# Serial_Hub.net
KiCad netlist of a schematic drawn in Altium Designer
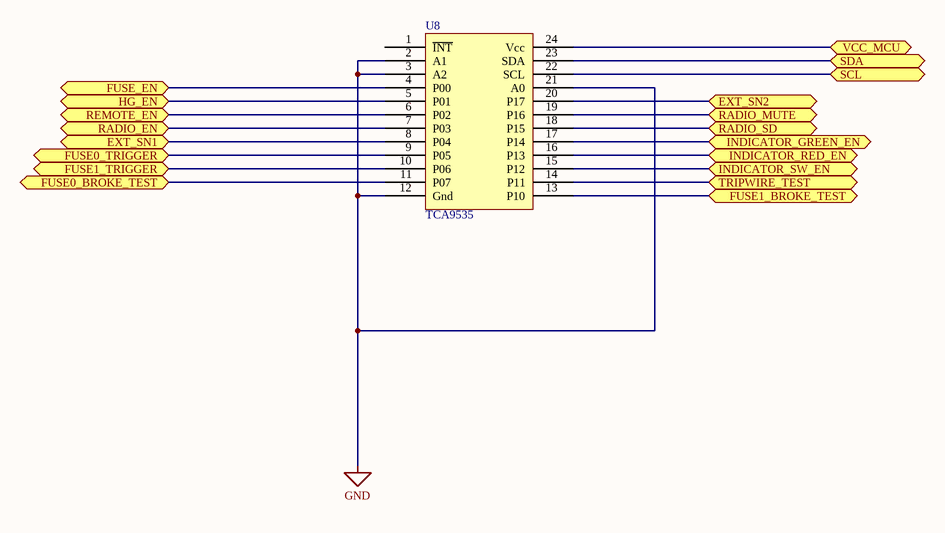
[diagram p0: Serial_Hub.SchDoc]

(export (version "E")
  (design (tool "Eeschema 10.0.6"))
  (components
    (comp (ref "U8") (value "TCA9535") (footprint "clock:TSSOP24") (libsource (lib "clock") (part "TCA9535")))
  )
  (nets
    (net (code "1") (name "/EXT_SN1") (class "Default")
      (node (ref "U8") (pin "8") (pinfunction "P04_8") (pintype "passive"))
    )
    (net (code "2") (name "/EXT_SN2") (class "Default")
      (node (ref "U8") (pin "20") (pinfunction "P17_20") (pintype "passive"))
    )
    (net (code "3") (name "/FUSE0_BROKE_TEST") (class "Default")
      (node (ref "U8") (pin "11") (pinfunction "P07_11") (pintype "passive"))
    )
    (net (code "4") (name "/FUSE0_TRIGGER") (class "Default")
      (node (ref "U8") (pin "9") (pinfunction "P05_9") (pintype "passive"))
    )
    (net (code "5") (name "/FUSE1_BROKE_TEST") (class "Default")
      (node (ref "U8") (pin "13") (pinfunction "P10_13") (pintype "passive"))
    )
    (net (code "6") (name "/FUSE1_TRIGGER") (class "Default")
      (node (ref "U8") (pin "10") (pinfunction "P06_10") (pintype "passive"))
    )
    (net (code "7") (name "/FUSE_EN") (class "Default")
      (node (ref "U8") (pin "4") (pinfunction "P00_4") (pintype "passive"))
    )
    (net (code "8") (name "/HG_EN") (class "Default")
      (node (ref "U8") (pin "5") (pinfunction "P01_5") (pintype "passive"))
    )
    (net (code "9") (name "/INDICATOR_GREEN_EN") (class "Default")
      (node (ref "U8") (pin "17") (pinfunction "P14_17") (pintype "passive"))
    )
    (net (code "10") (name "/INDICATOR_RED_EN") (class "Default")
      (node (ref "U8") (pin "16") (pinfunction "P13_16") (pintype "passive"))
    )
    (net (code "11") (name "/INDICATOR_SW_EN") (class "Default")
      (node (ref "U8") (pin "15") (pinfunction "P12_15") (pintype "passive"))
    )
    (net (code "12") (name "/RADIO_EN") (class "Default")
      (node (ref "U8") (pin "7") (pinfunction "P03_7") (pintype "passive"))
    )
    (net (code "13") (name "/RADIO_MUTE") (class "Default")
      (node (ref "U8") (pin "19") (pinfunction "P16_19") (pintype "passive"))
    )
    (net (code "14") (name "/RADIO_SD") (class "Default")
      (node (ref "U8") (pin "18") (pinfunction "P15_18") (pintype "passive"))
    )
    (net (code "15") (name "/REMOTE_EN") (class "Default")
      (node (ref "U8") (pin "6") (pinfunction "P02_6") (pintype "passive"))
    )
    (net (code "16") (name "/SCL") (class "Default")
      (node (ref "U8") (pin "22") (pinfunction "SCL_22") (pintype "passive"))
    )
    (net (code "17") (name "/SDA") (class "Default")
      (node (ref "U8") (pin "23") (pinfunction "SDA_23") (pintype "passive"))
    )
    (net (code "18") (name "/TRIPWIRE_TEST") (class "Default")
      (node (ref "U8") (pin "14") (pinfunction "P11_14") (pintype "passive"))
    )
    (net (code "19") (name "/VCC_MCU") (class "Default")
      (node (ref "U8") (pin "24") (pinfunction "Vcc_24") (pintype "passive"))
    )
    (net (code "20") (name "GND") (class "Default")
      (node (ref "U8") (pin "12") (pinfunction "Gnd_12") (pintype "passive"))
      (node (ref "U8") (pin "2") (pinfunction "A1_2") (pintype "passive"))
      (node (ref "U8") (pin "21") (pinfunction "A0_21") (pintype "passive"))
      (node (ref "U8") (pin "3") (pinfunction "A2_3") (pintype "passive"))
    )
    (net (code "21") (name "unconnected-(U8-~{INT}-Pad1)") (class "Default")
      (node (ref "U8") (pin "1") (pinfunction "~{INT}_1") (pintype "passive"))
    )
  )
)
